# MAGI_sWiFi.net
KiCad netlist of a schematic drawn in Altium Designer
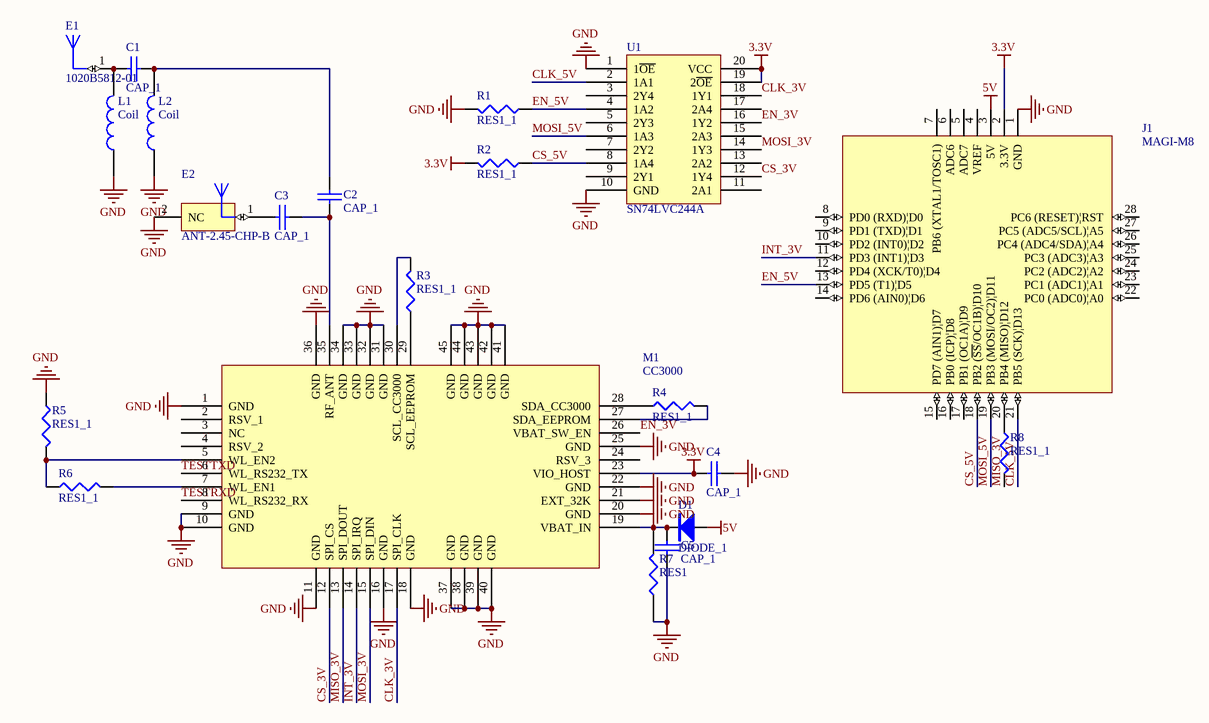
[diagram p0: MAGI'sWiFi.SchDoc]

(export (version "E")
  (design (tool "Eeschema 10.0.6"))
  (components
    (comp (ref "C1")
      (value "CAP_1")
      (footprint "1608[0603]")
      (description "Capacitor")
      (libsource (lib "电容器") (part "CAP_1"))
    )
    (comp (ref "C2")
      (value "CAP_1")
      (footprint "1608[0603]")
      (description "Capacitor")
      (libsource (lib "电容器") (part "CAP_1"))
    )
    (comp (ref "C3")
      (value "CAP_1")
      (footprint "1608[0603]")
      (description "Capacitor")
      (libsource (lib "电容器") (part "CAP_1"))
    )
    (comp (ref "C4")
      (value "CAP_1")
      (footprint "6-0805_N")
      (description "Capacitor")
      (libsource (lib "电容器") (part "CAP_1"))
    )
    (comp (ref "C5")
      (value "CAP_1")
      (footprint "6-0805_N")
      (description "Capacitor")
      (libsource (lib "电容器") (part "CAP_1"))
    )
    (comp (ref "D1")
      (value "DIODE_1")
      (footprint "SMA")
      (description "Diode")
      (libsource (lib "二极管") (part "DIODE_1"))
    )
    (comp (ref "E1")
      (value "1020B5812-01")
      (footprint "AT8010-E2R9HAA")
      (description "Flavus GSM Snap-In Antenna, 800/900/1800/1900 MHz, 0.8mm PCB Thickness")
      (fields (field (name "PUBLISHER") "Altium Limited"))
      (libsource (lib "Antenova RF and IF Antenna") (part "1020B5812-01"))
    )
    (comp (ref "E2")
      (value "ANT-2.45-CHP-B")
      (footprint "U.FL")
      (description "2.45GHz Ultra-Compact, LTCC, Chip Antenna, Bulk")
      (fields (field (name "PUBLISHER") "Altium Limited"))
      (libsource (lib "AF RF and IF Antenna") (part "ANT-2.45-CHP-B"))
    )
    (comp (ref "J1") (value "MAGI-M8") (footprint "MAGI-M8") (libsource (lib "MAGI-M8") (part "MAGI-M8")))
    (comp (ref "L1") (value "Coil") (footprint "1608[0603]") (libsource (lib "coil") (part "Coil")))
    (comp (ref "L2") (value "Coil") (footprint "1608[0603]") (libsource (lib "coil") (part "Coil")))
    (comp (ref "M1") (value "CC3000") (footprint "CC3000MOD") (libsource (lib "Modle") (part "CC3000")))
    (comp (ref "R1") (value "RES1_1") (footprint "6-0805_N") (libsource (lib "电阻器") (part "RES1_1")))
    (comp (ref "R2") (value "RES1_1") (footprint "6-0805_N") (libsource (lib "电阻器") (part "RES1_1")))
    (comp (ref "R3") (value "RES1_1") (footprint "1608[0603]") (libsource (lib "电阻器") (part "RES1_1")))
    (comp (ref "R4") (value "RES1_1") (footprint "1608[0603]") (libsource (lib "电阻器") (part "RES1_1")))
    (comp (ref "R5") (value "RES1_1") (footprint "1608[0603]") (libsource (lib "电阻器") (part "RES1_1")))
    (comp (ref "R6") (value "RES1_1") (footprint "1608[0603]") (libsource (lib "电阻器") (part "RES1_1")))
    (comp (ref "R7") (value "RES1") (footprint "6-0805_N") (libsource (lib "电阻器") (part "RES1")))
    (comp (ref "R8") (value "RES1_1") (footprint "1608[0603]") (libsource (lib "电阻器") (part "RES1_1")))
    (comp (ref "U1")
      (value "SN74LVC244A")
      (footprint "SN74LVC244APWRG")
      (libsource (lib "LogicIC") (part "74LVC244"))
    )
  )
  (nets
    (net (code "1") (name "/CLK_3V") (class "Default")
      (node (ref "M1") (pin "17") (pinfunction "SPI_CLK_17") (pintype "passive"))
      (node (ref "U1") (pin "18") (pinfunction "1Y1_18") (pintype "passive"))
    )
    (net (code "2") (name "/CLK_5V") (class "Default")
      (node (ref "J1") (pin "21") (pinfunction "PB5_(SCK)¦D13_21") (pintype "bidirectional"))
      (node (ref "U1") (pin "2") (pinfunction "1A1_2") (pintype "passive"))
    )
    (net (code "3") (name "/CS_3V") (class "Default")
      (node (ref "M1") (pin "12") (pinfunction "SPI_CS_12") (pintype "passive"))
      (node (ref "U1") (pin "12") (pinfunction "1Y4_12") (pintype "passive"))
    )
    (net (code "4") (name "/CS_5V") (class "Default")
      (node (ref "J1") (pin "18") (pinfunction "PB2_(~{SS}/OC1B)¦D10_18") (pintype "bidirectional"))
      (node (ref "R2") (pin "1") (pinfunction "1_1") (pintype "passive"))
      (node (ref "U1") (pin "8") (pinfunction "1A4_8") (pintype "passive"))
    )
    (net (code "5") (name "/EN_3V") (class "Default")
      (node (ref "M1") (pin "26") (pinfunction "VBAT_SW_EN_26") (pintype "passive"))
      (node (ref "U1") (pin "16") (pinfunction "1Y2_16") (pintype "passive"))
    )
    (net (code "6") (name "/EN_5V") (class "Default")
      (node (ref "J1") (pin "13") (pinfunction "PD5_(T1)¦D5_13") (pintype "bidirectional"))
      (node (ref "R1") (pin "1") (pinfunction "1_1") (pintype "passive"))
      (node (ref "U1") (pin "4") (pinfunction "1A2_4") (pintype "passive"))
    )
    (net (code "7") (name "/INT_3V") (class "Default")
      (node (ref "J1") (pin "11") (pinfunction "PD3_(INT1)¦D3_11") (pintype "bidirectional"))
      (node (ref "M1") (pin "14") (pinfunction "SPI_IRQ_14") (pintype "passive"))
    )
    (net (code "8") (name "/MISO_3V") (class "Default")
      (node (ref "M1") (pin "13") (pinfunction "SPI_DOUT_13") (pintype "passive"))
      (node (ref "R8") (pin "2") (pinfunction "2_2") (pintype "passive"))
    )
    (net (code "9") (name "/MOSI_3V") (class "Default")
      (node (ref "M1") (pin "15") (pinfunction "SPI_DIN_15") (pintype "passive"))
      (node (ref "U1") (pin "14") (pinfunction "1Y3_14") (pintype "passive"))
    )
    (net (code "10") (name "/MOSI_5V") (class "Default")
      (node (ref "J1") (pin "19") (pinfunction "PB3_(MOSI/OC2)¦D11_19") (pintype "bidirectional"))
      (node (ref "U1") (pin "6") (pinfunction "1A3_6") (pintype "passive"))
    )
    (net (code "11") (name "/TESTRXD") (class "Default")
      (node (ref "M1") (pin "8") (pinfunction "WL_RS232_RX_8") (pintype "passive"))
    )
    (net (code "12") (name "/TESTTXD") (class "Default")
      (node (ref "M1") (pin "6") (pinfunction "WL_RS232_TX_6") (pintype "passive"))
    )
    (net (code "13") (name "3.3V") (class "Default")
      (node (ref "C4") (pin "1") (pinfunction "1_1") (pintype "passive"))
      (node (ref "J1") (pin "2") (pinfunction "3.3V_2") (pintype "power_in"))
      (node (ref "M1") (pin "23") (pinfunction "VIO_HOST_23") (pintype "passive"))
      (node (ref "R2") (pin "2") (pinfunction "2_2") (pintype "passive"))
      (node (ref "U1") (pin "19") (pinfunction "2~{OE}_19") (pintype "passive"))
      (node (ref "U1") (pin "20") (pinfunction "VCC_20") (pintype "passive"))
    )
    (net (code "14") (name "5V") (class "Default")
      (node (ref "D1") (pin "1") (pinfunction "A_1") (pintype "passive"))
      (node (ref "J1") (pin "3") (pinfunction "5V_3") (pintype "power_in"))
    )
    (net (code "15") (name "GND") (class "Default")
      (node (ref "C4") (pin "2") (pinfunction "2_2") (pintype "passive"))
      (node (ref "C5") (pin "2") (pinfunction "2_2") (pintype "passive"))
      (node (ref "E2") (pin "2") (pinfunction "NC_2") (pintype "passive"))
      (node (ref "J1") (pin "1") (pinfunction "GND_1") (pintype "power_in"))
      (node (ref "L1") (pin "1") (pinfunction "1_1") (pintype "passive"))
      (node (ref "L2") (pin "1") (pinfunction "1_1") (pintype "passive"))
      (node (ref "M1") (pin "1") (pinfunction "GND_1") (pintype "passive"))
      (node (ref "M1") (pin "10") (pinfunction "GND_10") (pintype "passive"))
      (node (ref "M1") (pin "11") (pinfunction "GND_11") (pintype "passive"))
      (node (ref "M1") (pin "16") (pinfunction "GND_16") (pintype "passive"))
      (node (ref "M1") (pin "18") (pinfunction "GND_18") (pintype "passive"))
      (node (ref "M1") (pin "20") (pinfunction "GND_20") (pintype "passive"))
      (node (ref "M1") (pin "21") (pinfunction "EXT_32K_21") (pintype "passive"))
      (node (ref "M1") (pin "22") (pinfunction "GND_22") (pintype "passive"))
      (node (ref "M1") (pin "25") (pinfunction "GND_25") (pintype "passive"))
      (node (ref "M1") (pin "31") (pinfunction "GND_31") (pintype "passive"))
      (node (ref "M1") (pin "32") (pinfunction "GND_32") (pintype "passive"))
      (node (ref "M1") (pin "33") (pinfunction "GND_33") (pintype "passive"))
      (node (ref "M1") (pin "34") (pinfunction "GND_34") (pintype "passive"))
      (node (ref "M1") (pin "36") (pinfunction "GND_36") (pintype "passive"))
      (node (ref "M1") (pin "37") (pinfunction "GND_37") (pintype "passive"))
      (node (ref "M1") (pin "38") (pinfunction "GND_38") (pintype "passive"))
      (node (ref "M1") (pin "39") (pinfunction "GND_39") (pintype "passive"))
      (node (ref "M1") (pin "40") (pinfunction "GND_40") (pintype "passive"))
      (node (ref "M1") (pin "41") (pinfunction "GND_41") (pintype "passive"))
      (node (ref "M1") (pin "42") (pinfunction "GND_42") (pintype "passive"))
      (node (ref "M1") (pin "43") (pinfunction "GND_43") (pintype "passive"))
      (node (ref "M1") (pin "44") (pinfunction "GND_44") (pintype "passive"))
      (node (ref "M1") (pin "45") (pinfunction "GND_45") (pintype "passive"))
      (node (ref "M1") (pin "9") (pinfunction "GND_9") (pintype "passive"))
      (node (ref "R1") (pin "2") (pinfunction "2_2") (pintype "passive"))
      (node (ref "R5") (pin "1") (pinfunction "1_1") (pintype "passive"))
      (node (ref "R7") (pin "1") (pinfunction "1_1") (pintype "passive"))
      (node (ref "U1") (pin "1") (pinfunction "1~{OE}_1") (pintype "passive"))
      (node (ref "U1") (pin "10") (pinfunction "GND_10") (pintype "passive"))
    )
    (net (code "16") (name "Net-(C1-Pad1)") (class "Default")
      (node (ref "C1") (pin "1") (pinfunction "1_1") (pintype "passive"))
      (node (ref "C2") (pin "2") (pinfunction "2_2") (pintype "passive"))
      (node (ref "L2") (pin "2") (pinfunction "2_2") (pintype "passive"))
    )
    (net (code "17") (name "Net-(D1-K)") (class "Default")
      (node (ref "C5") (pin "1") (pinfunction "1_1") (pintype "passive"))
      (node (ref "D1") (pin "2") (pinfunction "K_2") (pintype "passive"))
      (node (ref "M1") (pin "19") (pinfunction "VBAT_IN_19") (pintype "passive"))
      (node (ref "R7") (pin "2") (pinfunction "2_2") (pintype "passive"))
    )
    (net (code "18") (name "Net-(E1-FEED)") (class "Default")
      (node (ref "C1") (pin "2") (pinfunction "2_2") (pintype "passive"))
      (node (ref "E1") (pin "1") (pinfunction "FEED_1") (pintype "bidirectional"))
      (node (ref "L1") (pin "2") (pinfunction "2_2") (pintype "passive"))
    )
    (net (code "19") (name "Net-(E2-FEED)") (class "Default")
      (node (ref "C3") (pin "2") (pinfunction "2_2") (pintype "passive"))
      (node (ref "E2") (pin "1") (pinfunction "FEED_1") (pintype "bidirectional"))
    )
    (net (code "20") (name "Net-(J1-PB4_(MISO)¦D12)") (class "Default")
      (node (ref "J1") (pin "20") (pinfunction "PB4_(MISO)¦D12_20") (pintype "bidirectional"))
      (node (ref "R8") (pin "1") (pinfunction "1_1") (pintype "passive"))
    )
    (net (code "21") (name "Net-(M1-RF_ANT)") (class "Default")
      (node (ref "C2") (pin "1") (pinfunction "1_1") (pintype "passive"))
      (node (ref "C3") (pin "1") (pinfunction "1_1") (pintype "passive"))
      (node (ref "M1") (pin "35") (pinfunction "RF_ANT_35") (pintype "passive"))
    )
    (net (code "22") (name "Net-(M1-SCL_CC3000)") (class "Default")
      (node (ref "M1") (pin "30") (pinfunction "SCL_CC3000_30") (pintype "passive"))
      (node (ref "R3") (pin "2") (pinfunction "2_2") (pintype "passive"))
    )
    (net (code "23") (name "Net-(M1-SCL_EEPROM)") (class "Default")
      (node (ref "M1") (pin "29") (pinfunction "SCL_EEPROM_29") (pintype "passive"))
      (node (ref "R3") (pin "1") (pinfunction "1_1") (pintype "passive"))
    )
    (net (code "24") (name "Net-(M1-SDA_CC3000)") (class "Default")
      (node (ref "M1") (pin "28") (pinfunction "SDA_CC3000_28") (pintype "passive"))
      (node (ref "R4") (pin "1") (pinfunction "1_1") (pintype "passive"))
    )
    (net (code "25") (name "Net-(M1-SDA_EEPROM)") (class "Default")
      (node (ref "M1") (pin "27") (pinfunction "SDA_EEPROM_27") (pintype "passive"))
      (node (ref "R4") (pin "2") (pinfunction "2_2") (pintype "passive"))
    )
    (net (code "26") (name "Net-(M1-WL_EN1)") (class "Default")
      (node (ref "M1") (pin "7") (pinfunction "WL_EN1_7") (pintype "passive"))
      (node (ref "R6") (pin "2") (pinfunction "2_2") (pintype "passive"))
    )
    (net (code "27") (name "Net-(M1-WL_EN2)") (class "Default")
      (node (ref "M1") (pin "5") (pinfunction "WL_EN2_5") (pintype "passive"))
      (node (ref "R5") (pin "2") (pinfunction "2_2") (pintype "passive"))
      (node (ref "R6") (pin "1") (pinfunction "1_1") (pintype "passive"))
    )
    (net (code "28") (name "unconnected-(J1-ADC6-Pad6)") (class "Default")
      (node (ref "J1") (pin "6") (pinfunction "ADC6_6") (pintype "passive"))
    )
    (net (code "29") (name "unconnected-(J1-ADC7-Pad5)") (class "Default")
      (node (ref "J1") (pin "5") (pinfunction "ADC7_5") (pintype "passive"))
    )
    (net (code "30") (name "unconnected-(J1-PB0_(ICP)¦D8-Pad16)") (class "Default")
      (node (ref "J1") (pin "16") (pinfunction "PB0_(ICP)¦D8_16") (pintype "bidirectional"))
    )
    (net (code "31") (name "unconnected-(J1-PB1_(OC1A)¦D9-Pad17)") (class "Default")
      (node (ref "J1") (pin "17") (pinfunction "PB1_(OC1A)¦D9_17") (pintype "bidirectional"))
    )
    (net (code "32") (name "unconnected-(J1-PB6_(XTAL1{slash}TOSC1)-Pad7)") (class "Default")
      (node (ref "J1") (pin "7") (pinfunction "PB6_(XTAL1/TOSC1)_7") (pintype "passive"))
    )
    (net (code "33") (name "unconnected-(J1-PC0_(ADC0)¦A0-Pad22)") (class "Default")
      (node (ref "J1") (pin "22") (pinfunction "PC0_(ADC0)¦A0_22") (pintype "bidirectional"))
    )
    (net (code "34") (name "unconnected-(J1-PC1_(ADC1)¦A1-Pad23)") (class "Default")
      (node (ref "J1") (pin "23") (pinfunction "PC1_(ADC1)¦A1_23") (pintype "bidirectional"))
    )
    (net (code "35") (name "unconnected-(J1-PC2_(ADC2)¦A2-Pad24)") (class "Default")
      (node (ref "J1") (pin "24") (pinfunction "PC2_(ADC2)¦A2_24") (pintype "bidirectional"))
    )
    (net (code "36") (name "unconnected-(J1-PC3_(ADC3)¦A3-Pad25)") (class "Default")
      (node (ref "J1") (pin "25") (pinfunction "PC3_(ADC3)¦A3_25") (pintype "bidirectional"))
    )
    (net (code "37") (name "unconnected-(J1-PC4_(ADC4{slash}SDA)¦A4-Pad26)") (class "Default")
      (node (ref "J1") (pin "26") (pinfunction "PC4_(ADC4/SDA)¦A4_26") (pintype "bidirectional"))
    )
    (net (code "38") (name "unconnected-(J1-PC5_(ADC5{slash}SCL)¦A5-Pad27)") (class "Default")
      (node (ref "J1") (pin "27") (pinfunction "PC5_(ADC5/SCL)¦A5_27") (pintype "bidirectional"))
    )
    (net (code "39") (name "unconnected-(J1-PC6_(RESET)¦RST-Pad28)") (class "Default")
      (node (ref "J1") (pin "28") (pinfunction "PC6_(RESET)¦RST_28") (pintype "bidirectional"))
    )
    (net (code "40") (name "unconnected-(J1-PD0_(RXD)¦D0-Pad8)") (class "Default")
      (node (ref "J1") (pin "8") (pinfunction "PD0_(RXD)¦D0_8") (pintype "bidirectional"))
    )
    (net (code "41") (name "unconnected-(J1-PD1_(TXD)¦D1-Pad9)") (class "Default")
      (node (ref "J1") (pin "9") (pinfunction "PD1_(TXD)¦D1_9") (pintype "bidirectional"))
    )
    (net (code "42") (name "unconnected-(J1-PD2_(INT0)¦D2-Pad10)") (class "Default")
      (node (ref "J1") (pin "10") (pinfunction "PD2_(INT0)¦D2_10") (pintype "bidirectional"))
    )
    (net (code "43") (name "unconnected-(J1-PD4_(XCK{slash}T0)¦D4-Pad12)") (class "Default")
      (node (ref "J1") (pin "12") (pinfunction "PD4_(XCK/T0)¦D4_12") (pintype "bidirectional"))
    )
    (net (code "44") (name "unconnected-(J1-PD6_(AIN0)¦D6-Pad14)") (class "Default")
      (node (ref "J1") (pin "14") (pinfunction "PD6_(AIN0)¦D6_14") (pintype "bidirectional"))
    )
    (net (code "45") (name "unconnected-(J1-PD7_(AIN1)¦D7-Pad15)") (class "Default")
      (node (ref "J1") (pin "15") (pinfunction "PD7_(AIN1)¦D7_15") (pintype "bidirectional"))
    )
    (net (code "46") (name "unconnected-(J1-VREF-Pad4)") (class "Default")
      (node (ref "J1") (pin "4") (pinfunction "VREF_4") (pintype "passive"))
    )
    (net (code "47") (name "unconnected-(M1-NC-Pad3)") (class "Default")
      (node (ref "M1") (pin "3") (pinfunction "NC_3") (pintype "passive"))
    )
    (net (code "48") (name "unconnected-(M1-RSV_1-Pad2)") (class "Default")
      (node (ref "M1") (pin "2") (pinfunction "RSV_1_2") (pintype "passive"))
    )
    (net (code "49") (name "unconnected-(M1-RSV_2-Pad4)") (class "Default")
      (node (ref "M1") (pin "4") (pinfunction "RSV_2_4") (pintype "passive"))
    )
    (net (code "50") (name "unconnected-(M1-RSV_3-Pad24)") (class "Default")
      (node (ref "M1") (pin "24") (pinfunction "RSV_3_24") (pintype "passive"))
    )
    (net (code "51") (name "unconnected-(U1-2A1-Pad11)") (class "Default")
      (node (ref "U1") (pin "11") (pinfunction "2A1_11") (pintype "passive"))
    )
    (net (code "52") (name "unconnected-(U1-2A2-Pad13)") (class "Default")
      (node (ref "U1") (pin "13") (pinfunction "2A2_13") (pintype "passive"))
    )
    (net (code "53") (name "unconnected-(U1-2A3-Pad15)") (class "Default")
      (node (ref "U1") (pin "15") (pinfunction "2A3_15") (pintype "passive"))
    )
    (net (code "54") (name "unconnected-(U1-2A4-Pad17)") (class "Default")
      (node (ref "U1") (pin "17") (pinfunction "2A4_17") (pintype "passive"))
    )
    (net (code "55") (name "unconnected-(U1-2Y1-Pad9)") (class "Default")
      (node (ref "U1") (pin "9") (pinfunction "2Y1_9") (pintype "passive"))
    )
    (net (code "56") (name "unconnected-(U1-2Y2-Pad7)") (class "Default")
      (node (ref "U1") (pin "7") (pinfunction "2Y2_7") (pintype "passive"))
    )
    (net (code "57") (name "unconnected-(U1-2Y3-Pad5)") (class "Default")
      (node (ref "U1") (pin "5") (pinfunction "2Y3_5") (pintype "passive"))
    )
    (net (code "58") (name "unconnected-(U1-2Y4-Pad3)") (class "Default")
      (node (ref "U1") (pin "3") (pinfunction "2Y4_3") (pintype "passive"))
    )
  )
)
